# Interconnect.net
KiCad netlist of a schematic drawn in Altium Designer
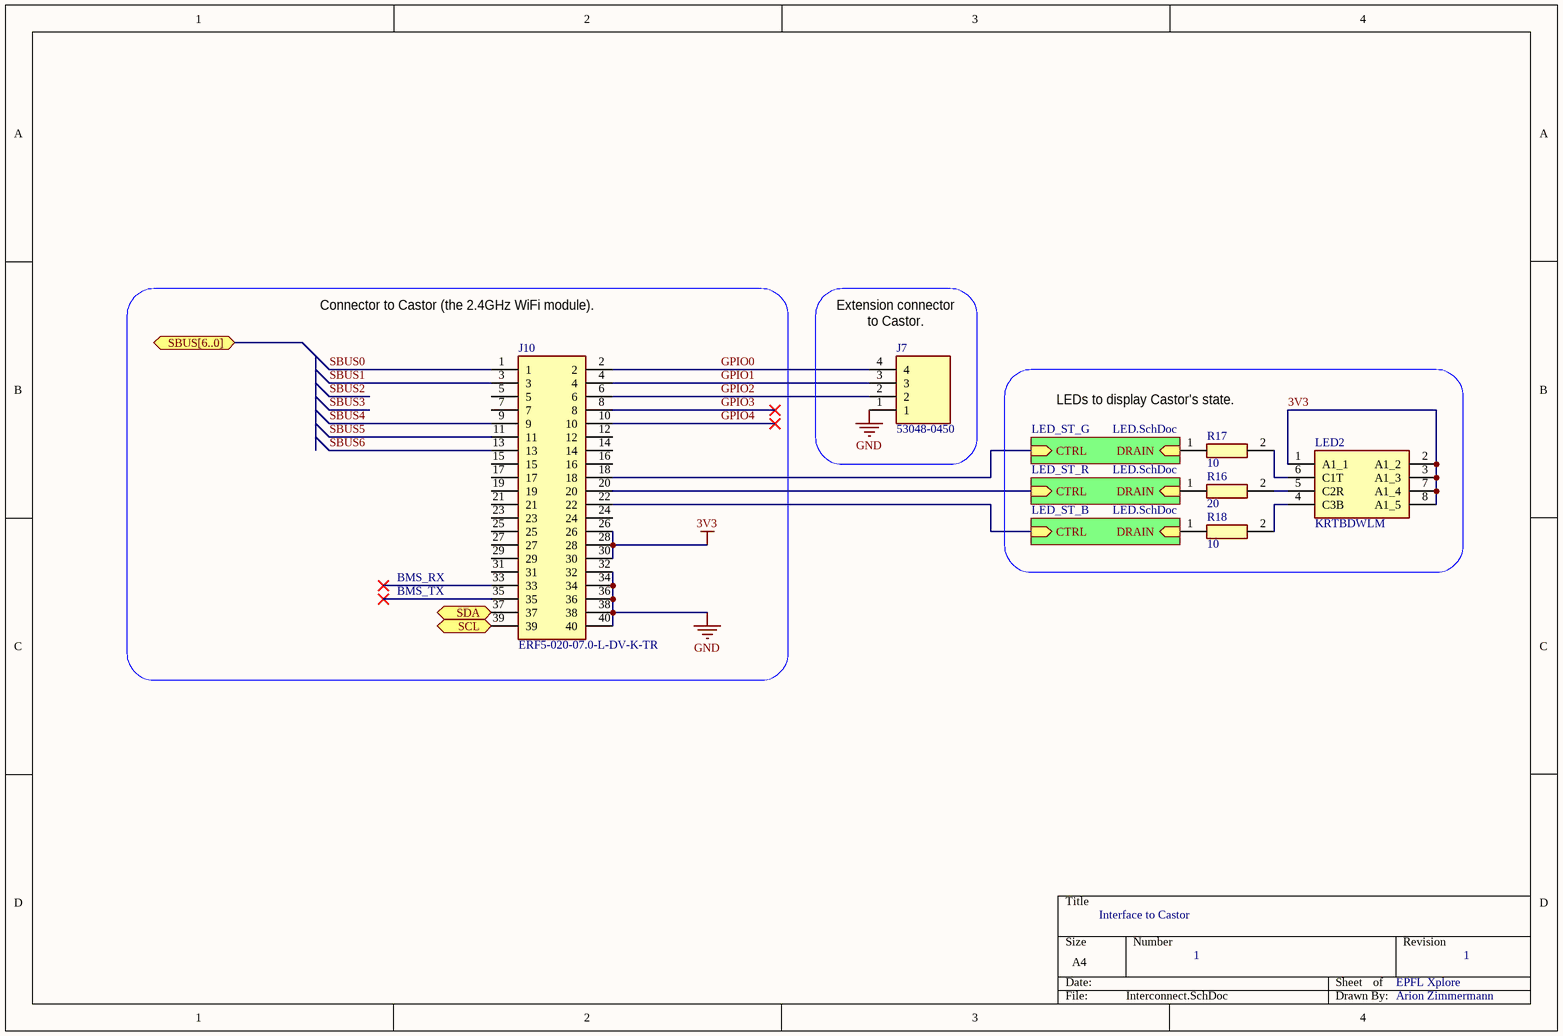
[diagram p0: Interconnect.SchDoc]

(export (version "E")
  (design (tool "Eeschema 10.0.6"))
  (components
    (comp (ref "J7")
      (value "53048-0450")
      (footprint "SHDRRA4W35P0X125_1X4_675X550X350P")
      (description "Connector")
      (fields (field (name "MOUSER PART NUMBER") "538-53048-0450"))
      (libsource (lib "*") (part "53048-0450"))
    )
    (comp (ref "J10")
      (value "ERF5-020-07.0-L-DV-K-TR")
      (footprint "SamacSys:ERF5-020-XX.X-Y-DV-K-TR")
      (description "Connector")
      (fields (field (name "MOUSER PART NUMBER") "200-ERF5020070LDVKTR"))
      (libsource (lib "SamacSys") (part "ERF5-020-07.0-L-DV-K-TR"))
    )
    (comp (ref "LED2")
      (value "KRTBDWLM")
      (footprint "SamacSys:KRTBDWLM3232T4U6JWAAABJ3R4S65V")
      (description "LED")
      (fields
        (field (name "MANUFACTURER_PART_NUMBER") "KRTBDWLM32.32-T4U6-JW+AAAB-J3+R4S6-5V")
        (field (name "MOUSER PART NUMBER") "720-KRTBDWLM323A7940")
      )
      (libsource (lib "CarrierBoard") (part "KRTBDWLM32.32-T4U6-JW+AAAB-J3+R4S6-5V"))
    )
    (comp (ref "R16")
      (value "20")
      (footprint "SamacSys:RESC1608X55N")
      (description "Resistor")
      (fields
        (field (name "MANUFACTURER_PART_NUMBER") "CRCW060320R0FKEAC")
        (field (name "MOUSER PART NUMBER") "71-CRCW060320R0FKEAC")
      )
      (libsource (lib "CarrierBoard") (part "CRCW060320R0FKEAC"))
    )
    (comp (ref "R17")
      (value "10")
      (footprint "SamacSys:RESC1608X55N")
      (description "Resistor")
      (fields
        (field (name "MANUFACTURER_PART_NUMBER") "CRCW060310R0FKEAC")
        (field (name "MOUSER PART NUMBER") "71-CRCW060310R0FKEAC")
      )
      (libsource (lib "CarrierBoard") (part "CRCW060310R0FKEAC"))
    )
    (comp (ref "R18")
      (value "10")
      (footprint "SamacSys:RESC1608X55N")
      (description "Resistor")
      (fields
        (field (name "MANUFACTURER_PART_NUMBER") "CRCW060310R0FKEAC")
        (field (name "MOUSER PART NUMBER") "71-CRCW060310R0FKEAC")
      )
      (libsource (lib "CarrierBoard") (part "CRCW060310R0FKEAC"))
    )
  )
  (nets
    (net (code "1") (name "/CTRL") (class "Default")
      (node (ref "J10") (pin "22") (pinfunction "22_22") (pintype "passive"))
    )
    (net (code "2") (name "/CTRL_1") (class "Default")
      (node (ref "J10") (pin "18") (pinfunction "18_18") (pintype "passive"))
    )
    (net (code "3") (name "/CTRL_2") (class "Default")
      (node (ref "J10") (pin "20") (pinfunction "20_20") (pintype "passive"))
    )
    (net (code "4") (name "/DRAIN") (class "Default")
      (node (ref "R16") (pin "1") (pinfunction "1_1") (pintype "passive"))
    )
    (net (code "5") (name "/DRAIN_1") (class "Default")
      (node (ref "R18") (pin "1") (pinfunction "1_1") (pintype "passive"))
    )
    (net (code "6") (name "/DRAIN_2") (class "Default")
      (node (ref "R17") (pin "1") (pinfunction "1_1") (pintype "passive"))
    )
    (net (code "7") (name "/GPIO0") (class "Default")
      (node (ref "J10") (pin "2") (pinfunction "2_2") (pintype "passive"))
      (node (ref "J7") (pin "4") (pinfunction "4_4") (pintype "passive"))
    )
    (net (code "8") (name "/GPIO1") (class "Default")
      (node (ref "J10") (pin "4") (pinfunction "4_4") (pintype "passive"))
      (node (ref "J7") (pin "3") (pinfunction "3_3") (pintype "passive"))
    )
    (net (code "9") (name "/GPIO2") (class "Default")
      (node (ref "J10") (pin "6") (pinfunction "6_6") (pintype "passive"))
      (node (ref "J7") (pin "2") (pinfunction "2_2") (pintype "passive"))
    )
    (net (code "10") (name "/GPIO3") (class "Default")
      (node (ref "J10") (pin "8") (pinfunction "8_8") (pintype "passive+no_connect"))
    )
    (net (code "11") (name "/GPIO4") (class "Default")
      (node (ref "J10") (pin "10") (pinfunction "10_10") (pintype "passive+no_connect"))
    )
    (net (code "12") (name "/SBUS0") (class "Default")
      (node (ref "J10") (pin "1") (pinfunction "1_1") (pintype "passive"))
    )
    (net (code "13") (name "/SBUS1") (class "Default")
      (node (ref "J10") (pin "3") (pinfunction "3_3") (pintype "passive"))
    )
    (net (code "16") (name "/SBUS4") (class "Default")
      (node (ref "J10") (pin "9") (pinfunction "9_9") (pintype "passive"))
    )
    (net (code "17") (name "/SBUS5") (class "Default")
      (node (ref "J10") (pin "11") (pinfunction "11_11") (pintype "passive"))
    )
    (net (code "18") (name "/SBUS6") (class "Default")
      (node (ref "J10") (pin "13") (pinfunction "13_13") (pintype "passive"))
    )
    (net (code "20") (name "/SCL") (class "Default")
      (node (ref "J10") (pin "39") (pinfunction "39_39") (pintype "passive"))
    )
    (net (code "21") (name "/SDA") (class "Default")
      (node (ref "J10") (pin "37") (pinfunction "37_37") (pintype "passive"))
    )
    (net (code "22") (name "3V3") (class "Default")
      (node (ref "J10") (pin "26") (pinfunction "26_26") (pintype "passive"))
      (node (ref "J10") (pin "28") (pinfunction "28_28") (pintype "passive"))
      (node (ref "J10") (pin "30") (pinfunction "30_30") (pintype "passive"))
      (node (ref "LED2") (pin "1") (pinfunction "A1_1_1") (pintype "passive"))
      (node (ref "LED2") (pin "2") (pinfunction "A1_2_2") (pintype "passive"))
      (node (ref "LED2") (pin "3") (pinfunction "A1_3_3") (pintype "passive"))
      (node (ref "LED2") (pin "7") (pinfunction "A1_4_7") (pintype "passive"))
      (node (ref "LED2") (pin "8") (pinfunction "A1_5_8") (pintype "passive"))
    )
    (net (code "23") (name "GND") (class "Default")
      (node (ref "J10") (pin "32") (pinfunction "32_32") (pintype "passive"))
      (node (ref "J10") (pin "34") (pinfunction "34_34") (pintype "passive"))
      (node (ref "J10") (pin "36") (pinfunction "36_36") (pintype "passive"))
      (node (ref "J10") (pin "38") (pinfunction "38_38") (pintype "passive"))
      (node (ref "J10") (pin "40") (pinfunction "40_40") (pintype "passive"))
      (node (ref "J7") (pin "1") (pinfunction "1_1") (pintype "passive"))
    )
    (net (code "24") (name "Net-(LED2-C1T)") (class "Default")
      (node (ref "LED2") (pin "6") (pinfunction "C1T_6") (pintype "passive"))
      (node (ref "R17") (pin "2") (pinfunction "2_2") (pintype "passive"))
    )
    (net (code "25") (name "Net-(LED2-C2R)") (class "Default")
      (node (ref "LED2") (pin "5") (pinfunction "C2R_5") (pintype "passive"))
      (node (ref "R16") (pin "2") (pinfunction "2_2") (pintype "passive"))
    )
    (net (code "26") (name "Net-(LED2-C3B)") (class "Default")
      (node (ref "LED2") (pin "4") (pinfunction "C3B_4") (pintype "passive"))
      (node (ref "R18") (pin "2") (pinfunction "2_2") (pintype "passive"))
    )
    (net (code "27") (name "unconnected-(J10-Pad5)") (class "Default")
      (node (ref "J10") (pin "5") (pinfunction "5_5") (pintype "passive"))
    )
    (net (code "28") (name "unconnected-(J10-Pad7)") (class "Default")
      (node (ref "J10") (pin "7") (pinfunction "7_7") (pintype "passive"))
    )
    (net (code "29") (name "unconnected-(J10-Pad12)") (class "Default")
      (node (ref "J10") (pin "12") (pinfunction "12_12") (pintype "passive"))
    )
    (net (code "30") (name "unconnected-(J10-Pad14)") (class "Default")
      (node (ref "J10") (pin "14") (pinfunction "14_14") (pintype "passive"))
    )
    (net (code "31") (name "unconnected-(J10-Pad15)") (class "Default")
      (node (ref "J10") (pin "15") (pinfunction "15_15") (pintype "passive"))
    )
    (net (code "32") (name "unconnected-(J10-Pad16)") (class "Default")
      (node (ref "J10") (pin "16") (pinfunction "16_16") (pintype "passive"))
    )
    (net (code "33") (name "unconnected-(J10-Pad17)") (class "Default")
      (node (ref "J10") (pin "17") (pinfunction "17_17") (pintype "passive"))
    )
    (net (code "34") (name "unconnected-(J10-Pad19)") (class "Default")
      (node (ref "J10") (pin "19") (pinfunction "19_19") (pintype "passive"))
    )
    (net (code "35") (name "unconnected-(J10-Pad21)") (class "Default")
      (node (ref "J10") (pin "21") (pinfunction "21_21") (pintype "passive"))
    )
    (net (code "36") (name "unconnected-(J10-Pad23)") (class "Default")
      (node (ref "J10") (pin "23") (pinfunction "23_23") (pintype "passive"))
    )
    (net (code "37") (name "unconnected-(J10-Pad24)") (class "Default")
      (node (ref "J10") (pin "24") (pinfunction "24_24") (pintype "passive"))
    )
    (net (code "38") (name "unconnected-(J10-Pad25)") (class "Default")
      (node (ref "J10") (pin "25") (pinfunction "25_25") (pintype "passive"))
    )
    (net (code "39") (name "unconnected-(J10-Pad27)") (class "Default")
      (node (ref "J10") (pin "27") (pinfunction "27_27") (pintype "passive"))
    )
    (net (code "40") (name "unconnected-(J10-Pad29)") (class "Default")
      (node (ref "J10") (pin "29") (pinfunction "29_29") (pintype "passive"))
    )
    (net (code "41") (name "unconnected-(J10-Pad31)") (class "Default")
      (node (ref "J10") (pin "31") (pinfunction "31_31") (pintype "passive"))
    )
    (net (code "42") (name "unconnected-(J10-Pad33)") (class "Default")
      (node (ref "J10") (pin "33") (pinfunction "33_33") (pintype "passive+no_connect"))
    )
    (net (code "43") (name "unconnected-(J10-Pad35)") (class "Default")
      (node (ref "J10") (pin "35") (pinfunction "35_35") (pintype "passive+no_connect"))
    )
  )
)
